# wisp-5-mcu.net
KiCad netlist of a schematic drawn in Altium Designer
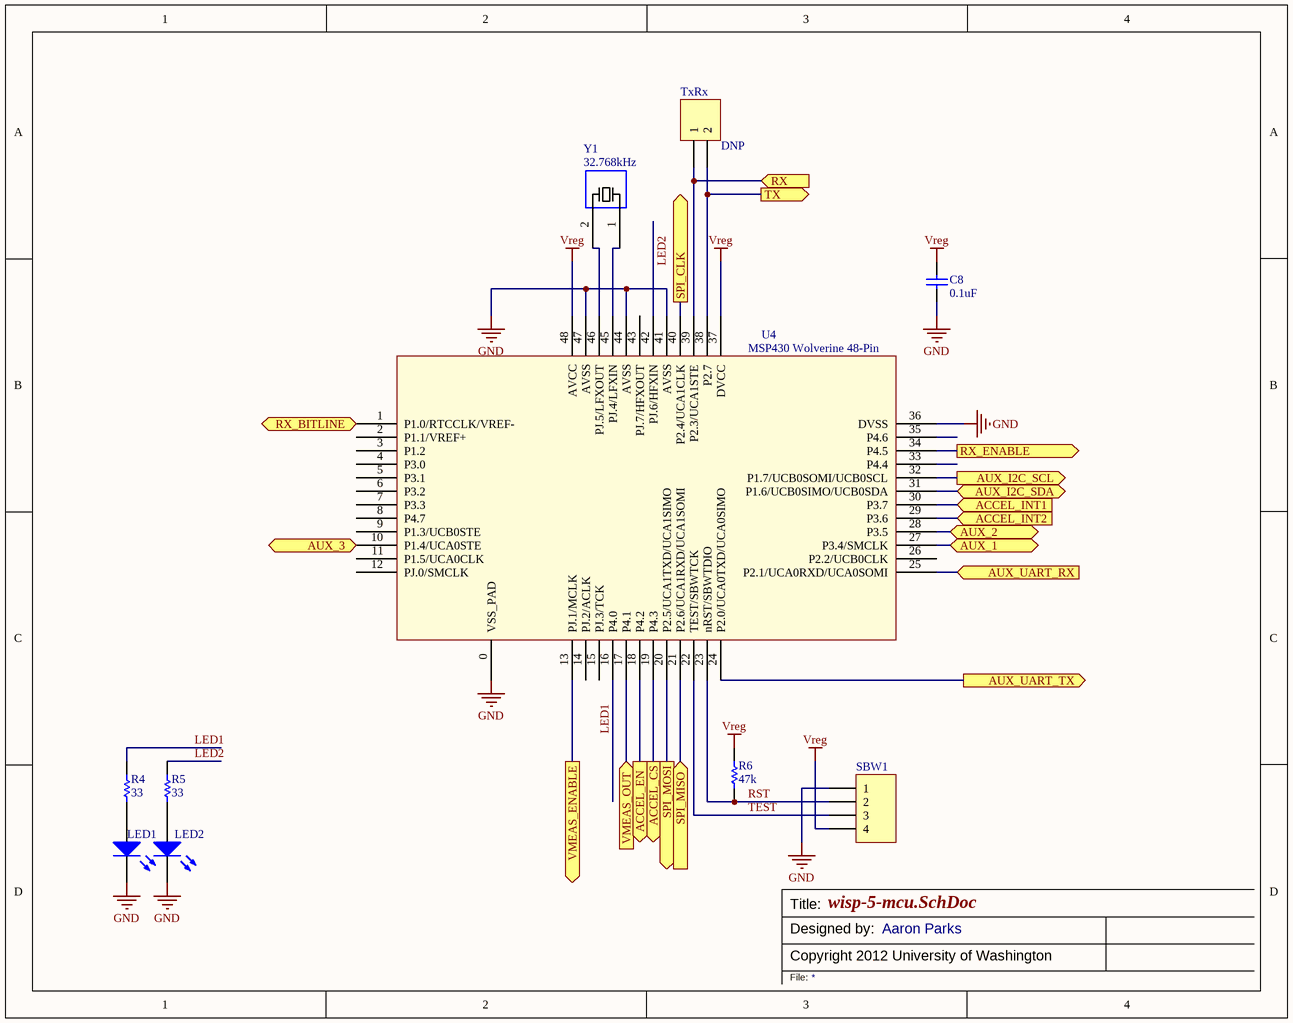
[diagram p0: wisp-5-mcu.SchDoc]

(export (version "E")
  (design (tool "Eeschema 10.0.6"))
  (components
    (comp (ref "C8")
      (value "0.1uF")
      (footprint "0402")
      (description "Ceramic Capacitor (Surface Mount)")
      (fields (field (name "DIGI-KEY PART NUMBER") "490-3261-1-ND") (field (name "MANUFACTURER") "Murata"))
      (libsource (lib "WISP_AD10") (part "Cap"))
    )
    (comp (ref "LED1")
      (value "LED")
      (footprint "Diode - 0603")
      (description "Typical RED, GREEN, YELLOW, AMBER GaAs LED")
      (fields (field (name "DIGI-KEY PART NUMBER") "475-2506-1-ND") (field (name "MANUFACTURER") "OSRAM"))
      (libsource (lib "WISP_AD10") (part "Diode - LED"))
    )
    (comp (ref "LED2")
      (value "LED")
      (footprint "Diode - 0603")
      (description "Typical RED, GREEN, YELLOW, AMBER GaAs LED")
      (fields (field (name "DIGI-KEY PART NUMBER") "475-2506-1-ND") (field (name "MANUFACTURER") "OSRAM"))
      (libsource (lib "WISP_AD10") (part "Diode - LED"))
    )
    (comp (ref "R4")
      (value "33")
      (footprint "0402")
      (description "Chip Resistor (Surface Mount)")
      (fields
        (field (name "MANUFACTURER") "Panasonic")
        (field (name "MANUFACTURER PART NUMBER") "ERJ-2RKF33R0X")
      )
      (libsource (lib "WISP_AD10") (part "Res"))
    )
    (comp (ref "R5")
      (value "33")
      (footprint "0402")
      (description "Chip Resistor (Surface Mount)")
      (fields
        (field (name "MANUFACTURER") "Panasonic")
        (field (name "MANUFACTURER PART NUMBER") "ERJ-2RKF33R0X")
      )
      (libsource (lib "WISP_AD10") (part "Res"))
    )
    (comp (ref "R6")
      (value "47k")
      (footprint "0402")
      (description "Chip Resistor (Surface Mount)")
      (fields
        (field (name "MANUFACTURER") "Panasonic")
        (field (name "MANUFACTURER PART NUMBER") "ERJ-2RKF4702X")
      )
      (libsource (lib "WISP_AD10") (part "Res"))
    )
    (comp (ref "SBW1")
      (value "4-Pin 0.05\" Pitch Female Rt Angle Header")
      (footprint "MHDR1X4")
      (description "Header, 4-Pin")
      (fields
        (field (name "MANUFACTURER PART NUMBER") "851-43-004-20-001000")
        (field (name "DIGI-KEY PART NUMBER") "ED90474-ND")
      )
      (libsource (lib "Miscellaneous Connectors") (part "MHDR1X4"))
    )
    (comp (ref "TxRx")
      (value "MHDR1X2")
      (footprint "MHDR1X2")
      (description "Header, 2-Pin")
      (fields (field (name "DNP") "DNP"))
      (libsource (lib "Miscellaneous Connectors") (part "MHDR1X2"))
    )
    (comp (ref "U4")
      (value "MSP430 Wolverine 48-Pin")
      (footprint "MSP_QFN48_RGZ_PAD0")
      (description "16-bit FRAM MCU")
      (fields
        (field (name "MANUFACTURER") "Texas Instruments")
        (field (name "MANUFACTURER PART NUMBER") "MSP430FR5969IRGZR")
      )
      (libsource (lib "WISP_AD10") (part "MSP430FR596X_586X_RGZ"))
    )
    (comp (ref "Y1")
      (value "32.768kHz")
      (footprint "XTAL [3.20mm x 1.50mm]")
      (description "Crystal Oscillator - [3.20mm x 1.50mm]")
      (fields
        (field (name "DIGI-KEY PART NUMBER") "SE2413CT-ND")
        (field (name "MANUFACTURER") "Epson Toyocom Corporation")
      )
      (libsource (lib "WISP_AD10") (part "XTAL 2-pins"))
    )
  )
  (nets
    (net (code "1") (name "/ACCEL_CS") (class "Default")
      (node (ref "U4") (pin "19") (pinfunction "P4.3_19") (pintype "passive"))
    )
    (net (code "2") (name "/ACCEL_EN") (class "Default")
      (node (ref "U4") (pin "18") (pinfunction "P4.2_18") (pintype "passive"))
    )
    (net (code "3") (name "/ACCEL_INT1") (class "Default")
      (node (ref "U4") (pin "30") (pinfunction "P3.7_30") (pintype "passive"))
    )
    (net (code "4") (name "/ACCEL_INT2") (class "Default")
      (node (ref "U4") (pin "29") (pinfunction "P3.6_29") (pintype "passive"))
    )
    (net (code "5") (name "/AUX_1") (class "Default")
      (node (ref "U4") (pin "27") (pinfunction "P3.4/SMCLK_27") (pintype "passive"))
    )
    (net (code "6") (name "/AUX_2") (class "Default")
      (node (ref "U4") (pin "28") (pinfunction "P3.5_28") (pintype "passive"))
    )
    (net (code "7") (name "/AUX_3") (class "Default")
      (node (ref "U4") (pin "10") (pinfunction "P1.4/UCA0STE_10") (pintype "passive"))
    )
    (net (code "8") (name "/AUX_I2C_SCL") (class "Default")
      (node (ref "U4") (pin "32") (pinfunction "P1.7/UCB0SOMI/UCB0SCL_32") (pintype "passive"))
    )
    (net (code "9") (name "/AUX_I2C_SDA") (class "Default")
      (node (ref "U4") (pin "31") (pinfunction "P1.6/UCB0SIMO/UCB0SDA_31") (pintype "passive"))
    )
    (net (code "10") (name "/AUX_UART_RX") (class "Default")
      (node (ref "U4") (pin "25") (pinfunction "P2.1/UCA0RXD/UCA0SOMI_25") (pintype "passive"))
    )
    (net (code "11") (name "/AUX_UART_TX") (class "Default")
      (node (ref "U4") (pin "24") (pinfunction "P2.0/UCA0TXD/UCA0SIMO_24") (pintype "passive"))
    )
    (net (code "12") (name "/LED1") (class "Default")
      (node (ref "R4") (pin "2") (pinfunction "2_2") (pintype "passive"))
      (node (ref "U4") (pin "16") (pinfunction "P4.0_16") (pintype "passive"))
    )
    (net (code "13") (name "/LED2") (class "Default")
      (node (ref "R5") (pin "2") (pinfunction "2_2") (pintype "passive"))
      (node (ref "U4") (pin "42") (pinfunction "PJ.6/HFXIN_42") (pintype "passive"))
    )
    (net (code "14") (name "/RST") (class "Default")
      (node (ref "R6") (pin "1") (pinfunction "1_1") (pintype "passive"))
      (node (ref "SBW1") (pin "2") (pinfunction "2_2") (pintype "passive"))
      (node (ref "U4") (pin "23") (pinfunction "nRST/SBWTDIO_23") (pintype "passive"))
    )
    (net (code "15") (name "/RX") (class "Default")
      (node (ref "TxRx") (pin "1") (pinfunction "1_1") (pintype "passive"))
      (node (ref "U4") (pin "39") (pinfunction "P2.3/UCA1STE_39") (pintype "passive"))
    )
    (net (code "16") (name "/RX_BITLINE") (class "Default")
      (node (ref "U4") (pin "1") (pinfunction "P1.0/RTCCLK/VREF-_1") (pintype "passive"))
    )
    (net (code "17") (name "/RX_ENABLE") (class "Default")
      (node (ref "U4") (pin "34") (pinfunction "P4.5_34") (pintype "passive"))
    )
    (net (code "18") (name "/SPI_CLK") (class "Default")
      (node (ref "U4") (pin "40") (pinfunction "P2.4/UCA1CLK_40") (pintype "passive"))
    )
    (net (code "19") (name "/SPI_MISO") (class "Default")
      (node (ref "U4") (pin "21") (pinfunction "P2.6/UCA1RXD/UCA1SOMI_21") (pintype "passive"))
    )
    (net (code "20") (name "/SPI_MOSI") (class "Default")
      (node (ref "U4") (pin "20") (pinfunction "P2.5/UCA1TXD/UCA1SIMO_20") (pintype "passive"))
    )
    (net (code "21") (name "/TEST") (class "Default")
      (node (ref "SBW1") (pin "3") (pinfunction "3_3") (pintype "passive"))
      (node (ref "U4") (pin "22") (pinfunction "TEST/SBWTCK_22") (pintype "passive"))
    )
    (net (code "22") (name "/TX") (class "Default")
      (node (ref "TxRx") (pin "2") (pinfunction "2_2") (pintype "passive"))
      (node (ref "U4") (pin "38") (pinfunction "P2.7_38") (pintype "passive"))
    )
    (net (code "23") (name "/VMEAS_ENABLE") (class "Default")
      (node (ref "U4") (pin "13") (pinfunction "PJ.1/MCLK_13") (pintype "passive"))
    )
    (net (code "24") (name "/VMEAS_OUT") (class "Default")
      (node (ref "U4") (pin "17") (pinfunction "P4.1_17") (pintype "passive"))
    )
    (net (code "25") (name "GND") (class "Default")
      (node (ref "C8") (pin "1") (pinfunction "1_1") (pintype "passive"))
      (node (ref "LED1") (pin "2") (pinfunction "K_2") (pintype "passive"))
      (node (ref "LED2") (pin "2") (pinfunction "K_2") (pintype "passive"))
      (node (ref "SBW1") (pin "1") (pinfunction "1_1") (pintype "passive"))
      (node (ref "U4") (pin "0") (pinfunction "VSS_PAD_0") (pintype "passive"))
      (node (ref "U4") (pin "36") (pinfunction "DVSS_36") (pintype "passive"))
      (node (ref "U4") (pin "41") (pinfunction "AVSS_41") (pintype "passive"))
      (node (ref "U4") (pin "44") (pinfunction "AVSS_44") (pintype "passive"))
      (node (ref "U4") (pin "47") (pinfunction "AVSS_47") (pintype "passive"))
    )
    (net (code "26") (name "Net-(LED1-A)") (class "Default")
      (node (ref "LED1") (pin "1") (pinfunction "A_1") (pintype "passive"))
      (node (ref "R4") (pin "1") (pinfunction "1_1") (pintype "passive"))
    )
    (net (code "27") (name "Net-(LED2-A)") (class "Default")
      (node (ref "LED2") (pin "1") (pinfunction "A_1") (pintype "passive"))
      (node (ref "R5") (pin "1") (pinfunction "1_1") (pintype "passive"))
    )
    (net (code "28") (name "Net-(U4-PJ.4{slash}LFXIN)") (class "Default")
      (node (ref "U4") (pin "45") (pinfunction "PJ.4/LFXIN_45") (pintype "passive"))
      (node (ref "Y1") (pin "1") (pinfunction "1_1") (pintype "power_in"))
    )
    (net (code "29") (name "Net-(U4-PJ.5{slash}LFXOUT)") (class "Default")
      (node (ref "U4") (pin "46") (pinfunction "PJ.5/LFXOUT_46") (pintype "passive"))
      (node (ref "Y1") (pin "2") (pinfunction "2_2") (pintype "power_in"))
    )
    (net (code "30") (name "Vreg") (class "Default")
      (node (ref "C8") (pin "2") (pinfunction "2_2") (pintype "passive"))
      (node (ref "R6") (pin "2") (pinfunction "2_2") (pintype "passive"))
      (node (ref "SBW1") (pin "4") (pinfunction "4_4") (pintype "passive"))
      (node (ref "U4") (pin "37") (pinfunction "DVCC_37") (pintype "passive"))
      (node (ref "U4") (pin "48") (pinfunction "AVCC_48") (pintype "passive"))
    )
    (net (code "31") (name "unconnected-(U4-P1.1{slash}VREF+-Pad2)") (class "Default")
      (node (ref "U4") (pin "2") (pinfunction "P1.1/VREF+_2") (pintype "passive"))
    )
    (net (code "32") (name "unconnected-(U4-P1.2-Pad3)") (class "Default")
      (node (ref "U4") (pin "3") (pinfunction "P1.2_3") (pintype "passive"))
    )
    (net (code "33") (name "unconnected-(U4-P1.3{slash}UCB0STE-Pad9)") (class "Default")
      (node (ref "U4") (pin "9") (pinfunction "P1.3/UCB0STE_9") (pintype "passive"))
    )
    (net (code "34") (name "unconnected-(U4-P1.5{slash}UCA0CLK-Pad11)") (class "Default")
      (node (ref "U4") (pin "11") (pinfunction "P1.5/UCA0CLK_11") (pintype "passive"))
    )
    (net (code "35") (name "unconnected-(U4-P2.2{slash}UCB0CLK-Pad26)") (class "Default")
      (node (ref "U4") (pin "26") (pinfunction "P2.2/UCB0CLK_26") (pintype "passive"))
    )
    (net (code "36") (name "unconnected-(U4-P3.0-Pad4)") (class "Default")
      (node (ref "U4") (pin "4") (pinfunction "P3.0_4") (pintype "passive"))
    )
    (net (code "37") (name "unconnected-(U4-P3.1-Pad5)") (class "Default")
      (node (ref "U4") (pin "5") (pinfunction "P3.1_5") (pintype "passive"))
    )
    (net (code "38") (name "unconnected-(U4-P3.2-Pad6)") (class "Default")
      (node (ref "U4") (pin "6") (pinfunction "P3.2_6") (pintype "passive"))
    )
    (net (code "39") (name "unconnected-(U4-P3.3-Pad7)") (class "Default")
      (node (ref "U4") (pin "7") (pinfunction "P3.3_7") (pintype "passive"))
    )
    (net (code "40") (name "unconnected-(U4-P4.4-Pad33)") (class "Default")
      (node (ref "U4") (pin "33") (pinfunction "P4.4_33") (pintype "passive"))
    )
    (net (code "41") (name "unconnected-(U4-P4.6-Pad35)") (class "Default")
      (node (ref "U4") (pin "35") (pinfunction "P4.6_35") (pintype "passive"))
    )
    (net (code "42") (name "unconnected-(U4-P4.7-Pad8)") (class "Default")
      (node (ref "U4") (pin "8") (pinfunction "P4.7_8") (pintype "passive"))
    )
    (net (code "43") (name "unconnected-(U4-PJ.0{slash}SMCLK-Pad12)") (class "Default")
      (node (ref "U4") (pin "12") (pinfunction "PJ.0/SMCLK_12") (pintype "passive"))
    )
    (net (code "44") (name "unconnected-(U4-PJ.2{slash}ACLK-Pad14)") (class "Default")
      (node (ref "U4") (pin "14") (pinfunction "PJ.2/ACLK_14") (pintype "passive"))
    )
    (net (code "45") (name "unconnected-(U4-PJ.3{slash}TCK-Pad15)") (class "Default")
      (node (ref "U4") (pin "15") (pinfunction "PJ.3/TCK_15") (pintype "passive"))
    )
    (net (code "46") (name "unconnected-(U4-PJ.7{slash}HFXOUT-Pad43)") (class "Default")
      (node (ref "U4") (pin "43") (pinfunction "PJ.7/HFXOUT_43") (pintype "passive"))
    )
  )
)
